# BEP31_RPM_BAR_switchedRES.net
KiCad netlist of a schematic drawn in EAGLE
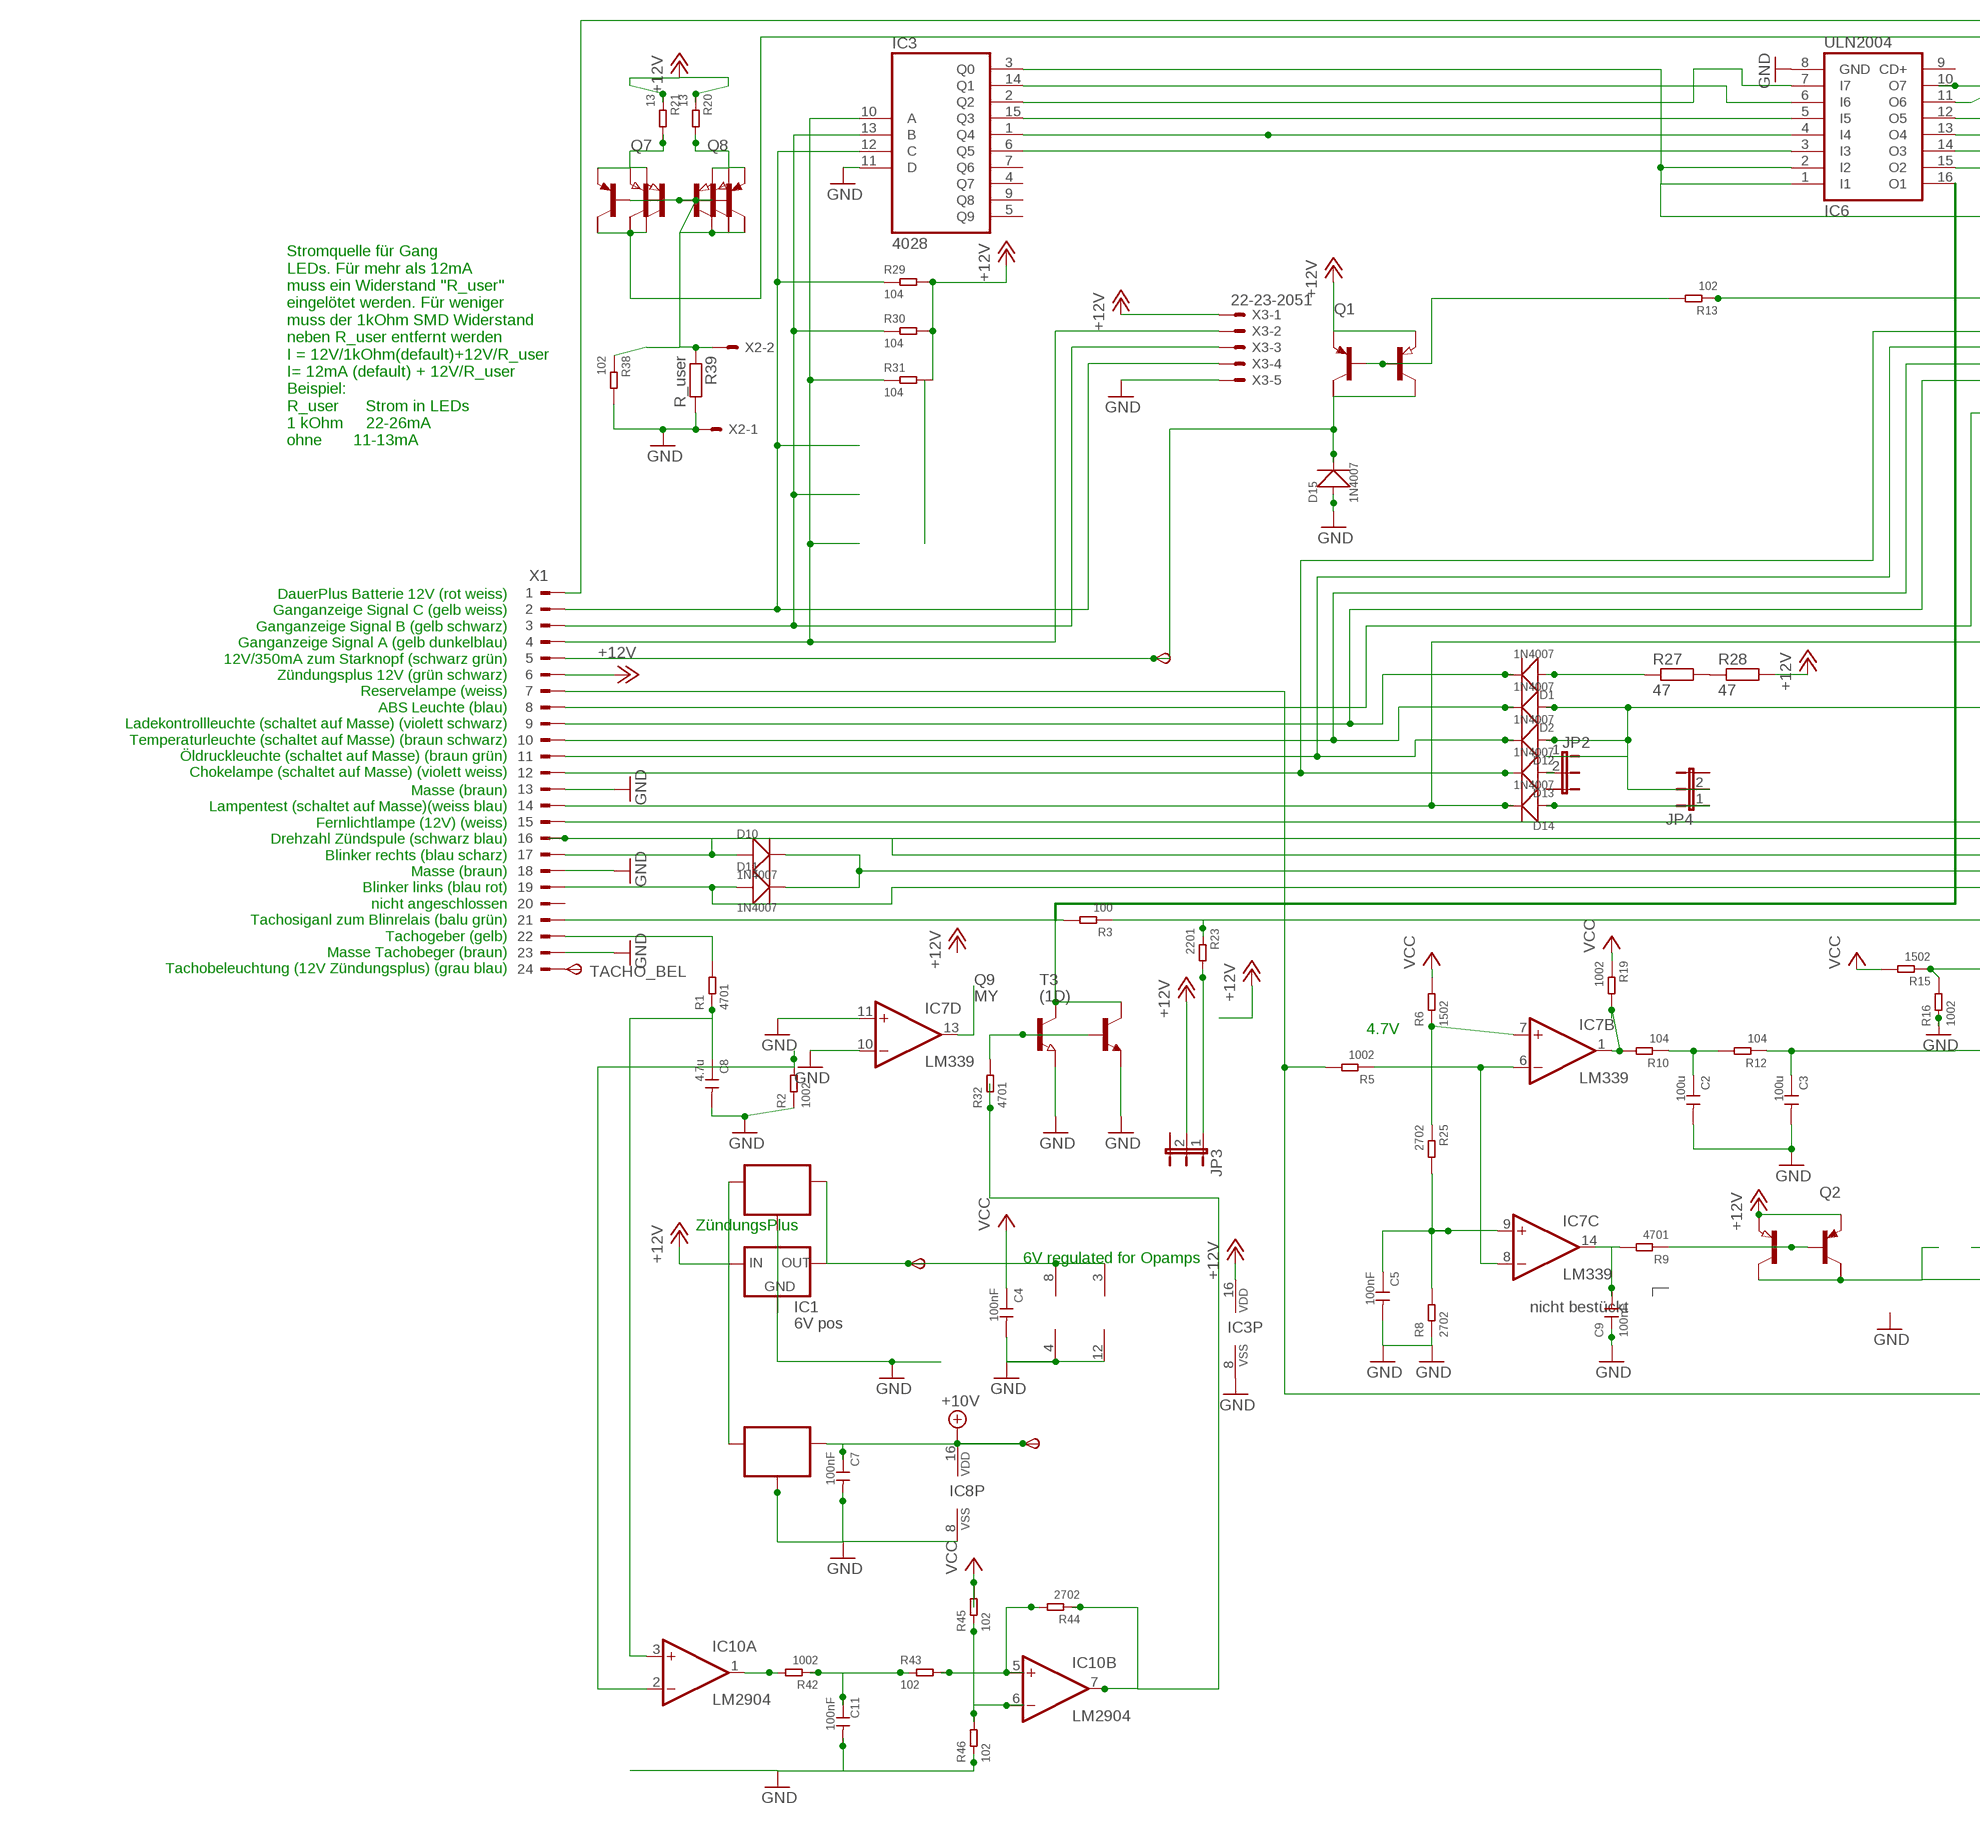
[diagram p0: schematic, sheet 1, part 1 of 2]
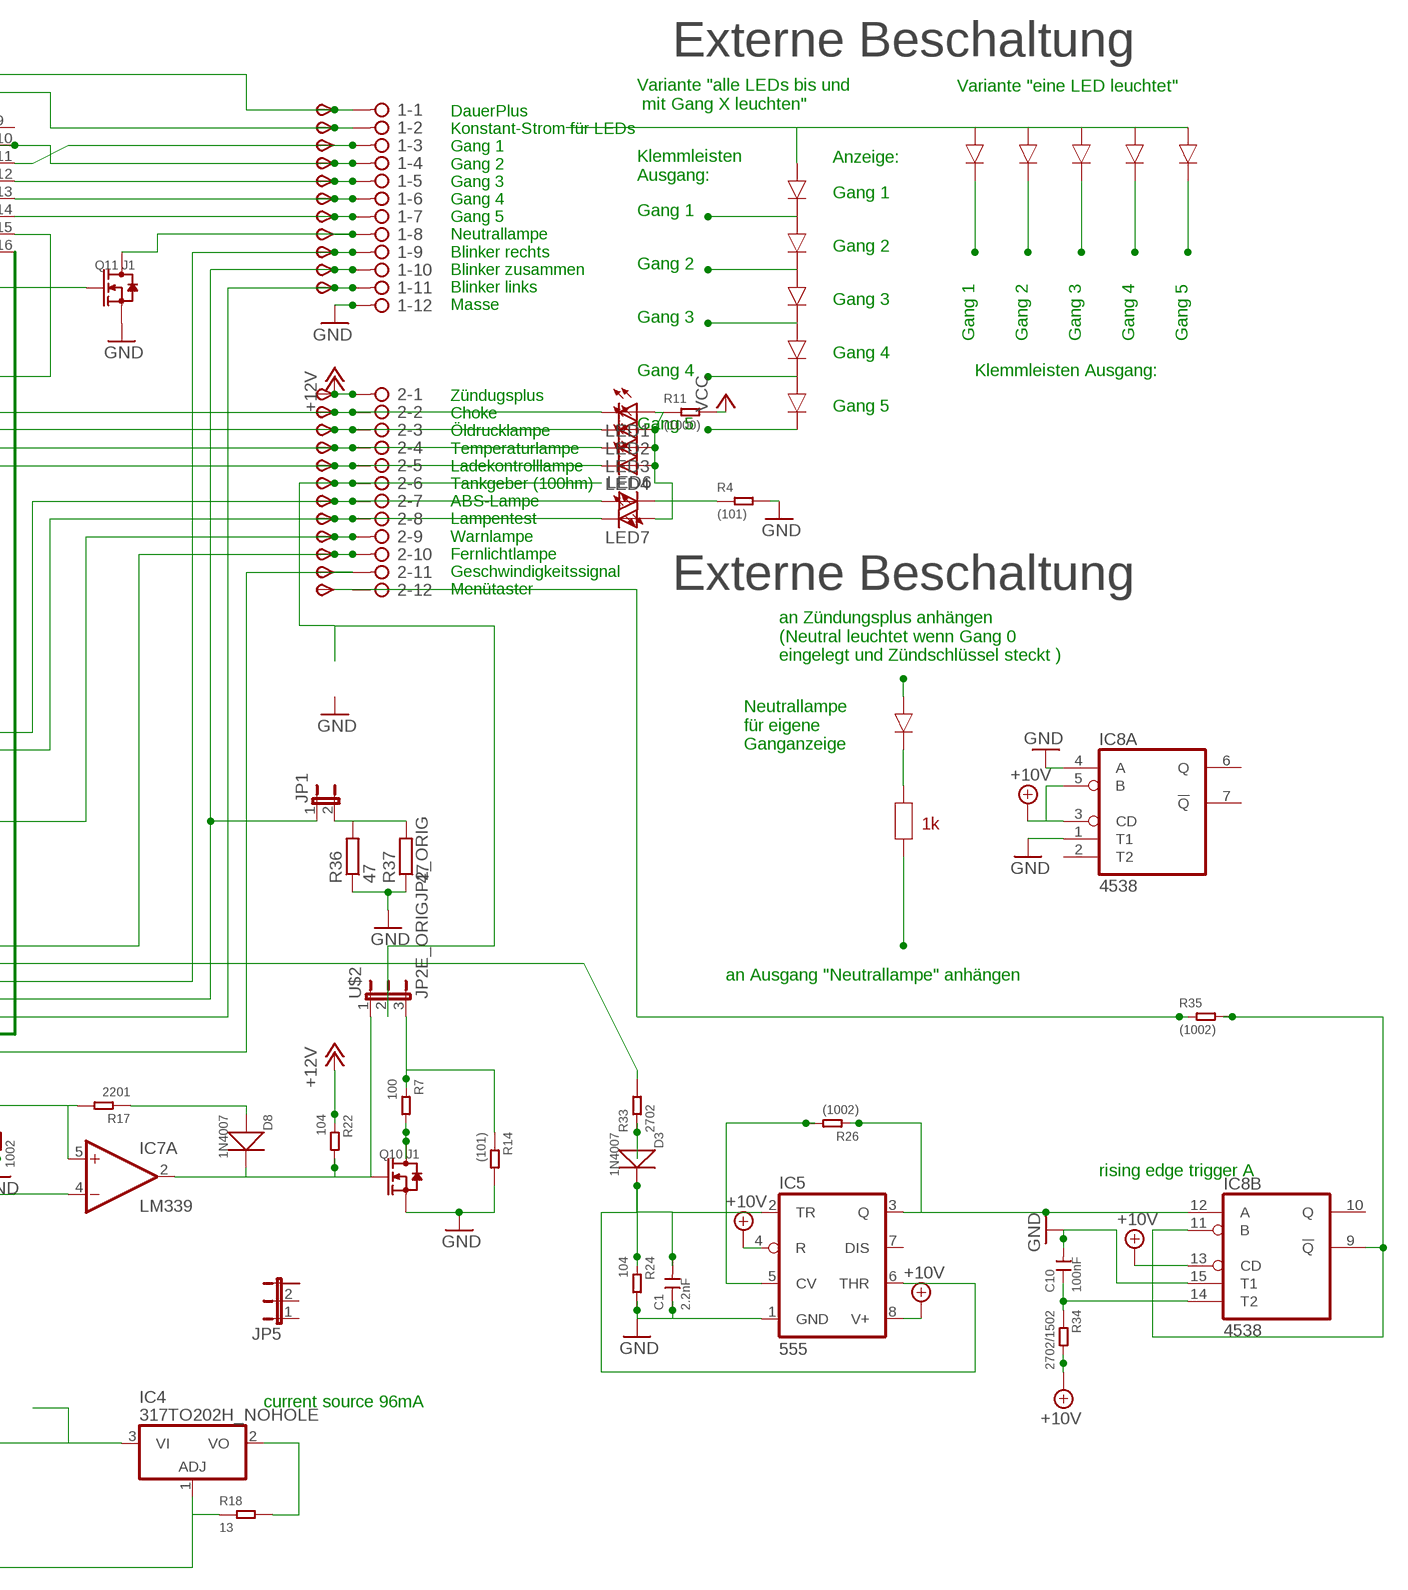
[diagram p1: schematic, sheet 1, part 2 of 2]

(export (version "E")
  (design (tool "Eeschema 10.0.6"))
  (components
    (comp (ref "1")
      (value "2081-1132")
      (footprint "eagle-import:12-PIN")
      (libsource (lib "eagle-import") (part "2081-1132"))
    )
    (comp (ref "2")
      (value "2081-1132")
      (footprint "eagle-import:12-PIN")
      (libsource (lib "eagle-import") (part "2081-1132"))
    )
    (comp (ref "6V")
      (value "TPSB1.8")
      (footprint "eagle-import:B1.8")
      (libsource (lib "eagle-import") (part "TPSB1.8"))
    )
    (comp (ref "10V")
      (value "TPSB1.8")
      (footprint "eagle-import:B1.8")
      (libsource (lib "eagle-import") (part "TPSB1.8"))
    )
    (comp (ref "C1")
      (value "2.2nF")
      (footprint "eagle-import:C0805")
      (fields (field (name "MPN") "CC0805KRX7R9BB104"))
      (libsource (lib "eagle-import") (part "CERAMIC-100NF-50V-10%-X7R(0805)"))
    )
    (comp (ref "C2")
      (value "100u")
      (footprint "eagle-import:C1206")
      (fields (field (name "MPN") "GRM31CR60J107ME39L"))
      (libsource (lib "eagle-import") (part "CERAMIC-100UF-6.3V-20%-X5R(1206)"))
    )
    (comp (ref "C3")
      (value "100u")
      (footprint "eagle-import:C1206")
      (fields (field (name "MPN") "GRM31CR60J107ME39L"))
      (libsource (lib "eagle-import") (part "CERAMIC-100UF-6.3V-20%-X5R(1206)"))
    )
    (comp (ref "C4")
      (value "100nF")
      (footprint "eagle-import:C0805")
      (fields (field (name "MPN") "CC0805KRX7R9BB104"))
      (libsource (lib "eagle-import") (part "CERAMIC-100NF-50V-10%-X7R(0805)"))
    )
    (comp (ref "C5")
      (value "100nF")
      (footprint "eagle-import:C0805")
      (fields (field (name "MPN") "CC0805KRX7R9BB104"))
      (libsource (lib "eagle-import") (part "CERAMIC-100NF-50V-10%-X7R(0805)"))
    )
    (comp (ref "C7")
      (value "100nF")
      (footprint "eagle-import:C0805")
      (fields (field (name "MPN") "CC0805KRX7R9BB104"))
      (libsource (lib "eagle-import") (part "CERAMIC-100NF-50V-10%-X7R(0805)"))
    )
    (comp (ref "C8")
      (value "4.7u")
      (footprint "eagle-import:C0805")
      (fields (field (name "MPN") "CC0805KKX5R8BB475"))
      (libsource (lib "eagle-import") (part "CERAMIC-4.7UF-25V-10%-X5R(0805)"))
    )
    (comp (ref "C9")
      (value "100nF")
      (footprint "eagle-import:C0805")
      (fields (field (name "MPN") "CC0805KRX7R9BB104"))
      (libsource (lib "eagle-import") (part "CERAMIC-100NF-50V-10%-X7R(0805)"))
    )
    (comp (ref "C10")
      (value "100nF")
      (footprint "eagle-import:C0805")
      (fields (field (name "MPN") "CC0805KRX7R9BB104"))
      (libsource (lib "eagle-import") (part "CERAMIC-100NF-50V-10%-X7R(0805)"))
    )
    (comp (ref "C11")
      (value "100nF")
      (footprint "eagle-import:C0805")
      (fields (field (name "MPN") "CC0805KRX7R9BB104"))
      (libsource (lib "eagle-import") (part "CERAMIC-100NF-50V-10%-X7R(0805)"))
    )
    (comp (ref "D1")
      (value "1N4007")
      (footprint "eagle-import:DO-214AC")
      (libsource (lib "eagle-import") (part "DIODE-GEN-PURPOSE-1KV-1A(DO-214AC)"))
    )
    (comp (ref "D2")
      (value "1N4007")
      (footprint "eagle-import:DO-214AC-1206MOUNT")
      (libsource (lib "eagle-import") (part "DIODE-GEN-PURPOSE-1KV-1A(DO-214AC)DO-214AC/1206"))
    )
    (comp (ref "D3")
      (value "1N4007")
      (footprint "eagle-import:DO-214AC")
      (libsource (lib "eagle-import") (part "DIODE-GEN-PURPOSE-1KV-1A(DO-214AC)"))
    )
    (comp (ref "D8")
      (value "1N4007")
      (footprint "eagle-import:DO-214AC")
      (libsource (lib "eagle-import") (part "DIODE-GEN-PURPOSE-1KV-1A(DO-214AC)"))
    )
    (comp (ref "D10")
      (value "1N4007")
      (footprint "eagle-import:DO-214AC")
      (libsource (lib "eagle-import") (part "DIODE-GEN-PURPOSE-1KV-1A(DO-214AC)"))
    )
    (comp (ref "D11")
      (value "1N4007")
      (footprint "eagle-import:DO-214AC")
      (libsource (lib "eagle-import") (part "DIODE-GEN-PURPOSE-1KV-1A(DO-214AC)"))
    )
    (comp (ref "D12")
      (value "1N4007")
      (footprint "eagle-import:DO-214AC-1206MOUNT")
      (libsource (lib "eagle-import") (part "DIODE-GEN-PURPOSE-1KV-1A(DO-214AC)DO-214AC/1206"))
    )
    (comp (ref "D13")
      (value "1N4007")
      (footprint "eagle-import:DO-214AC-1206MOUNT")
      (libsource (lib "eagle-import") (part "DIODE-GEN-PURPOSE-1KV-1A(DO-214AC)DO-214AC/1206"))
    )
    (comp (ref "D14")
      (value "1N4007")
      (footprint "eagle-import:DO-214AC-1206MOUNT")
      (libsource (lib "eagle-import") (part "DIODE-GEN-PURPOSE-1KV-1A(DO-214AC)DO-214AC/1206"))
    )
    (comp (ref "D15")
      (value "1N4007")
      (footprint "eagle-import:DO-214AC")
      (libsource (lib "eagle-import") (part "DIODE-GEN-PURPOSE-1KV-1A(DO-214AC)"))
    )
    (comp (ref "IC1")
      (value "6V pos")
      (footprint "eagle-import:78LXX")
      (libsource (lib "eagle-import") (part "v-reg_78LXX"))
    )
    (comp (ref "IC2")
      (value "78LXXSOT89_ROUND")
      (footprint "eagle-import:SOT89_ROUND")
      (libsource (lib "eagle-import") (part "78LXXSOT89_ROUND"))
    )
    (comp (ref "IC3")
      (value "4028")
      (footprint "eagle-import:SO16")
      (libsource (lib "eagle-import") (part "4028D"))
    )
    (comp (ref "IC4")
      (value "317TO202H_NOHOLE")
      (footprint "eagle-import:TO220H_NOHOLE")
      (libsource (lib "eagle-import") (part "317TO202H_NOHOLE"))
    )
    (comp (ref "IC5")
      (value "555")
      (footprint "eagle-import:SO08")
      (libsource (lib "eagle-import") (part "555DNE"))
    )
    (comp (ref "IC6")
      (value "ULN2004")
      (footprint "eagle-import:SO16")
      (libsource (lib "eagle-import") (part "ULN2004AD"))
    )
    (comp (ref "IC7")
      (value "LM339")
      (footprint "eagle-import:SO14")
      (libsource (lib "eagle-import") (part "LM339D"))
    )
    (comp (ref "IC8")
      (value "4538")
      (footprint "eagle-import:SO16")
      (libsource (lib "eagle-import") (part "4538D"))
    )
    (comp (ref "IC9")
      (value "78LXXSOT89_ROUND")
      (footprint "eagle-import:SOT89_ROUND")
      (libsource (lib "eagle-import") (part "78LXXSOT89_ROUND"))
    )
    (comp (ref "IC10")
      (value "LM2904")
      (footprint "eagle-import:SO08")
      (libsource (lib "eagle-import") (part "LM358D"))
    )
    (comp (ref "JP1")
      (value "JP1E")
      (footprint "eagle-import:JP1")
      (libsource (lib "eagle-import") (part "JP1E"))
    )
    (comp (ref "JP2")
      (value "JP2E")
      (footprint "eagle-import:JP2")
      (libsource (lib "eagle-import") (part "JP2E"))
    )
    (comp (ref "JP3")
      (value "JP2E")
      (footprint "eagle-import:JP2")
      (libsource (lib "eagle-import") (part "JP2E"))
    )
    (comp (ref "JP4")
      (value "JP2E")
      (footprint "eagle-import:JP2")
      (libsource (lib "eagle-import") (part "JP2E"))
    )
    (comp (ref "JP5")
      (value "JP2E")
      (footprint "eagle-import:JP2")
      (libsource (lib "eagle-import") (part "JP2E"))
    )
    (comp (ref "LED1")
      (value "LEDLD260")
      (footprint "eagle-import:LD260")
      (libsource (lib "eagle-import") (part "LEDLD260"))
    )
    (comp (ref "LED2")
      (value "LEDLD260")
      (footprint "eagle-import:LD260")
      (libsource (lib "eagle-import") (part "LEDLD260"))
    )
    (comp (ref "LED3")
      (value "LEDLD260")
      (footprint "eagle-import:LD260")
      (libsource (lib "eagle-import") (part "LEDLD260"))
    )
    (comp (ref "LED4")
      (value "LEDLD260")
      (footprint "eagle-import:LD260")
      (libsource (lib "eagle-import") (part "LEDLD260"))
    )
    (comp (ref "LED6")
      (value "LEDLD260")
      (footprint "eagle-import:LD260")
      (libsource (lib "eagle-import") (part "LEDLD260"))
    )
    (comp (ref "LED7")
      (value "LEDLD260")
      (footprint "eagle-import:LD260")
      (libsource (lib "eagle-import") (part "LEDLD260"))
    )
    (comp (ref "Q1")
      (value "PNP-TRANSISTOR_SOT89")
      (footprint "eagle-import:SOT89")
      (libsource (lib "eagle-import") (part "PNP-TRANSISTOR_SOT89"))
    )
    (comp (ref "Q2")
      (value "PNP-TRANSISTOR_SOT89")
      (footprint "eagle-import:SOT89")
      (libsource (lib "eagle-import") (part "PNP-TRANSISTOR_SOT89"))
    )
    (comp (ref "Q3")
      (value "AH-16")
      (footprint "eagle-import:SOT223")
      (libsource (lib "eagle-import") (part "BCP53T1"))
    )
    (comp (ref "Q4")
      (value "(AH-16)")
      (footprint "eagle-import:SOT223")
      (libsource (lib "eagle-import") (part "BCP53T1"))
    )
    (comp (ref "Q5")
      (value "(AH-16)")
      (footprint "eagle-import:SOT223")
      (libsource (lib "eagle-import") (part "BCP53T1"))
    )
    (comp (ref "Q6")
      (value "(AH-16)")
      (footprint "eagle-import:SOT223")
      (libsource (lib "eagle-import") (part "BCP53T1"))
    )
    (comp (ref "Q7")
      (value "PNP-TRANSISTOR_SOT89")
      (footprint "eagle-import:SOT89")
      (libsource (lib "eagle-import") (part "PNP-TRANSISTOR_SOT89"))
    )
    (comp (ref "Q8")
      (value "PNP-TRANSISTOR_SOT89")
      (footprint "eagle-import:SOT89")
      (libsource (lib "eagle-import") (part "PNP-TRANSISTOR_SOT89"))
    )
    (comp (ref "Q9")
      (value "MY")
      (footprint "eagle-import:SOT89")
      (libsource (lib "eagle-import") (part "NPN-TRANSISTOR_SOT89"))
    )
    (comp (ref "Q10")
      (value "J1")
      (footprint "eagle-import:SOT-23")
      (fields (field (name "MPN") "BSS138W-7-F"))
      (libsource (lib "eagle-import") (part "SMD-MOSFET-N-CH-50V-200MA-BSS138W-7-F(SOT-23)"))
    )
    (comp (ref "Q11")
      (value "J1")
      (footprint "eagle-import:SOT-23")
      (fields (field (name "MPN") "BSS138W-7-F"))
      (libsource (lib "eagle-import") (part "SMD-MOSFET-N-CH-50V-200MA-BSS138W-7-F(SOT-23)"))
    )
    (comp (ref "R1")
      (value "4701")
      (footprint "eagle-import:R0805")
      (fields (field (name "MPN") "RC0805JR-074K7L"))
      (libsource (lib "eagle-import") (part "SMD-RES-4.7K-5%-1/8W(0805)"))
    )
    (comp (ref "R2")
      (value "1002")
      (footprint "eagle-import:R0805")
      (fields (field (name "MPN") "RC0805FR-0710KL"))
      (libsource (lib "eagle-import") (part "SMD-RES-10K-1%-1/8W(0805)"))
    )
    (comp (ref "R3")
      (value "100")
      (footprint "eagle-import:R0805")
      (fields (field (name "MPN") "RC0805JR-07220RL"))
      (libsource (lib "eagle-import") (part "SMD-RES-220R-5%-1/8W(0805)"))
    )
    (comp (ref "R4")
      (value "(101)")
      (footprint "eagle-import:R0805")
      (fields (field (name "MPN") "RC0805JR-07100RL"))
      (libsource (lib "eagle-import") (part "SMD-RES-100R-5%-1/8W(0805)"))
    )
    (comp (ref "R5")
      (value "1002")
      (footprint "eagle-import:R0805")
      (fields (field (name "MPN") "RC0805FR-0710KL"))
      (libsource (lib "eagle-import") (part "SMD-RES-10K-1%-1/8W(0805)"))
    )
    (comp (ref "R6")
      (value "1502")
      (footprint "eagle-import:R0805")
      (fields (field (name "MPN") "RC0805FR-0710KL"))
      (libsource (lib "eagle-import") (part "SMD-RES-10K-1%-1/8W(0805)"))
    )
    (comp (ref "R7")
      (value "100")
      (footprint "eagle-import:R0805")
      (fields (field (name "MPN") "RC0805JR-072K2L"))
      (libsource (lib "eagle-import") (part "SMD-RES-2.2K-5%-1/8W(0805)"))
    )
    (comp (ref "R8")
      (value "2702")
      (footprint "eagle-import:R0805")
      (fields (field (name "MPN") "RC0805JR-074K7L"))
      (libsource (lib "eagle-import") (part "SMD-RES-4.7K-5%-1/8W(0805)"))
    )
    (comp (ref "R9")
      (value "4701")
      (footprint "eagle-import:R0805")
      (fields (field (name "MPN") "RC0805JR-074K7L"))
      (libsource (lib "eagle-import") (part "SMD-RES-4.7K-5%-1/8W(0805)"))
    )
    (comp (ref "R10")
      (value "104")
      (footprint "eagle-import:R0805")
      (fields (field (name "MPN") "RC0805FR-0710KL"))
      (libsource (lib "eagle-import") (part "SMD-RES-10K-1%-1/8W(0805)"))
    )
    (comp (ref "R11")
      (value "(1000)")
      (footprint "eagle-import:R0805")
      (fields (field (name "MPN") "RC0805JR-07100RL"))
      (libsource (lib "eagle-import") (part "SMD-RES-100R-5%-1/8W(0805)"))
    )
    (comp (ref "R12")
      (value "104")
      (footprint "eagle-import:R0805")
      (fields (field (name "MPN") "RC0805FR-0710KL"))
      (libsource (lib "eagle-import") (part "SMD-RES-10K-1%-1/8W(0805)"))
    )
    (comp (ref "R13")
      (value "102")
      (footprint "eagle-import:R0805")
      (fields (field (name "MPN") "RC0805JR-071KL"))
      (libsource (lib "eagle-import") (part "SMD-RES-1K-5%-1/8W(0805)"))
    )
    (comp (ref "R14")
      (value "(101)")
      (footprint "eagle-import:R0805")
      (fields (field (name "MPN") "RC0805JR-072K2L"))
      (libsource (lib "eagle-import") (part "SMD-RES-2.2K-5%-1/8W(0805)"))
    )
    (comp (ref "R15")
      (value "1502")
      (footprint "eagle-import:R0805")
      (fields (field (name "MPN") "RC0805FR-0710KL"))
      (libsource (lib "eagle-import") (part "SMD-RES-10K-1%-1/8W(0805)"))
    )
    (comp (ref "R16")
      (value "1002")
      (footprint "eagle-import:R0805")
      (fields (field (name "MPN") "RC0805FR-0710KL"))
      (libsource (lib "eagle-import") (part "SMD-RES-10K-1%-1/8W(0805)"))
    )
    (comp (ref "R17")
      (value "2201")
      (footprint "eagle-import:R0805")
      (fields (field (name "MPN") "RC0805JR-072K2L"))
      (libsource (lib "eagle-import") (part "SMD-RES-2.2K-5%-1/8W(0805)"))
    )
    (comp (ref "R18")
      (value "13")
      (footprint "eagle-import:R1206")
      (fields (field (name "MPN") "RC1206JR-0713RL"))
      (libsource (lib "eagle-import") (part "SMD-RES-13R-5%-1/4W(1206)"))
    )
    (comp (ref "R19")
      (value "1002")
      (footprint "eagle-import:R0805")
      (fields (field (name "MPN") "RC0805FR-0710KL"))
      (libsource (lib "eagle-import") (part "SMD-RES-10K-1%-1/8W(0805)"))
    )
    (comp (ref "R20")
      (value "13")
      (footprint "eagle-import:R1206")
      (fields (field (name "MPN") "RC1206JR-0713RL"))
      (libsource (lib "eagle-import") (part "SMD-RES-13R-5%-1/4W(1206)"))
    )
    (comp (ref "R21")
      (value "13")
      (footprint "eagle-import:R1206")
      (fields (field (name "MPN") "RC1206JR-0713RL"))
      (libsource (lib "eagle-import") (part "SMD-RES-13R-5%-1/4W(1206)"))
    )
    (comp (ref "R22")
      (value "104")
      (footprint "eagle-import:R0805")
      (fields (field (name "MPN") "RC0805FR-0710KL"))
      (libsource (lib "eagle-import") (part "SMD-RES-10K-1%-1/8W(0805)"))
    )
    (comp (ref "R23")
      (value "2201")
      (footprint "eagle-import:R0805")
      (fields (field (name "MPN") "RC0805JR-072K2L"))
      (libsource (lib "eagle-import") (part "SMD-RES-2.2K-5%-1/8W(0805)"))
    )
    (comp (ref "R24")
      (value "104")
      (footprint "eagle-import:R0805")
      (fields (field (name "MPN") "RC0805FR-0710KL"))
      (libsource (lib "eagle-import") (part "SMD-RES-10K-1%-1/8W(0805)"))
    )
    (comp (ref "R25")
      (value "2702")
      (footprint "eagle-import:R0805")
      (fields (field (name "MPN") "RC0805JR-074K7L"))
      (libsource (lib "eagle-import") (part "SMD-RES-4.7K-5%-1/8W(0805)"))
    )
    (comp (ref "R26")
      (value "(1002)")
      (footprint "eagle-import:R0805")
      (fields (field (name "MPN") "RC0805FR-0710KL"))
      (libsource (lib "eagle-import") (part "SMD-RES-10K-1%-1/8W(0805)"))
    )
    (comp (ref "R27")
      (value "47")
      (footprint "eagle-import:V235_17_1MM")
      (libsource (lib "eagle-import") (part "R-EU_V235/17_1MM"))
    )
    (comp (ref "R28")
      (value "47")
      (footprint "eagle-import:V235_17_1MM")
      (libsource (lib "eagle-import") (part "R-EU_V235/17_1MM"))
    )
    (comp (ref "R29")
      (value "104")
      (footprint "eagle-import:R0805")
      (fields (field (name "MPN") "RC0805FR-0710KL"))
      (libsource (lib "eagle-import") (part "SMD-RES-10K-1%-1/8W(0805)"))
    )
    (comp (ref "R30")
      (value "104")
      (footprint "eagle-import:R0805")
      (fields (field (name "MPN") "RC0805FR-0710KL"))
      (libsource (lib "eagle-import") (part "SMD-RES-10K-1%-1/8W(0805)"))
    )
    (comp (ref "R31")
      (value "104")
      (footprint "eagle-import:R0805")
      (fields (field (name "MPN") "RC0805FR-0710KL"))
      (libsource (lib "eagle-import") (part "SMD-RES-10K-1%-1/8W(0805)"))
    )
    (comp (ref "R32")
      (value "4701")
      (footprint "eagle-import:R0805")
      (fields (field (name "MPN") "RC0805JR-074K7L"))
      (libsource (lib "eagle-import") (part "SMD-RES-4.7K-5%-1/8W(0805)"))
    )
    (comp (ref "R33")
      (value "2702")
      (footprint "eagle-import:R0805")
      (fields (field (name "MPN") "RC0805FR-0710KL"))
      (libsource (lib "eagle-import") (part "SMD-RES-10K-1%-1/8W(0805)"))
    )
    (comp (ref "R34")
      (value "2702/1502")
      (footprint "eagle-import:R0805")
      (fields (field (name "MPN") "RC0805JR-074K7L"))
      (libsource (lib "eagle-import") (part "SMD-RES-4.7K-5%-1/8W(0805)"))
    )
    (comp (ref "R35")
      (value "(1002)")
      (footprint "eagle-import:R0805")
      (fields (field (name "MPN") "RC0805JR-074K7L"))
      (libsource (lib "eagle-import") (part "SMD-RES-4.7K-5%-1/8W(0805)"))
    )
    (comp (ref "R36")
      (value "47")
      (footprint "eagle-import:V235_17_1MM")
      (libsource (lib "eagle-import") (part "R-EU_V235/17_1MM"))
    )
    (comp (ref "R37")
      (value "47")
      (footprint "eagle-import:V235_17_1MM")
      (libsource (lib "eagle-import") (part "R-EU_V235/17_1MM"))
    )
    (comp (ref "R38")
      (value "102")
      (footprint "eagle-import:R0805")
      (fields (field (name "MPN") "RC0805JR-071KL"))
      (libsource (lib "eagle-import") (part "SMD-RES-1K-5%-1/8W(0805)"))
    )
    (comp (ref "R39")
      (value "R_user")
      (footprint "eagle-import:R0805")
      (libsource (lib "eagle-import") (part "R-EU_R0805"))
    )
    (comp (ref "R42")
      (value "1002")
      (footprint "eagle-import:R0805")
      (fields (field (name "MPN") "RC0805FR-0710KL"))
      (libsource (lib "eagle-import") (part "SMD-RES-10K-1%-1/8W(0805)"))
    )
    (comp (ref "R43")
      (value "102")
      (footprint "eagle-import:R0805")
      (fields (field (name "MPN") "RC0805JR-071KL"))
      (libsource (lib "eagle-import") (part "SMD-RES-1K-5%-1/8W(0805)"))
    )
    (comp (ref "R44")
      (value "2702")
      (footprint "eagle-import:R0805")
      (fields (field (name "MPN") "RC0805JR-074K7L"))
      (libsource (lib "eagle-import") (part "SMD-RES-4.7K-5%-1/8W(0805)"))
    )
    (comp (ref "R45")
      (value "102")
      (footprint "eagle-import:R0805")
      (fields (field (name "MPN") "RC0805JR-071KL"))
      (libsource (lib "eagle-import") (part "SMD-RES-1K-5%-1/8W(0805)"))
    )
    (comp (ref "R46")
      (value "102")
      (footprint "eagle-import:R0805")
      (fields (field (name "MPN") "RC0805JR-071KL"))
      (libsource (lib "eagle-import") (part "SMD-RES-1K-5%-1/8W(0805)"))
    )
    (comp (ref "START")
      (value "TPSB1.8")
      (footprint "eagle-import:B1.8")
      (libsource (lib "eagle-import") (part "TPSB1.8"))
    )
    (comp (ref "T1")
      (value "PNP2SM8")
      (footprint "eagle-import:SM8")
      (libsource (lib "eagle-import") (part "PNP2SM8"))
    )
    (comp (ref "T3")
      (value "(1D)")
      (footprint "eagle-import:SOT23-BEC")
      (libsource (lib "eagle-import") (part "-NPN-SOT23-BECMMBTA42LT1"))
    )
    (comp (ref "TACHO_BEL")
      (value "TPSP1_1MM")
      (footprint "eagle-import:P1_1.0MM")
      (libsource (lib "eagle-import") (part "TPSP1_1MM"))
    )
    (comp (ref "TP1")
      (value "TPSB1.8")
      (footprint "eagle-import:B1.8")
      (libsource (lib "eagle-import") (part "TPSB1.8"))
    )
    (comp (ref "TP2")
      (value "TPSB1.8")
      (footprint "eagle-import:B1.8")
      (libsource (lib "eagle-import") (part "TPSB1.8"))
    )
    (comp (ref "TP3")
      (value "TPSB1.8")
      (footprint "eagle-import:B1.8")
      (libsource (lib "eagle-import") (part "TPSB1.8"))
    )
    (comp (ref "TP4")
      (value "TPSB1.8")
      (footprint "eagle-import:B1.8")
      (libsource (lib "eagle-import") (part "TPSB1.8"))
    )
    (comp (ref "TP5")
      (value "TPSB1.8")
      (footprint "eagle-import:B1.8")
      (libsource (lib "eagle-import") (part "TPSB1.8"))
    )
    (comp (ref "TP6")
      (value "TPSB1.8")
      (footprint "eagle-import:B1.8")
      (libsource (lib "eagle-import") (part "TPSB1.8"))
    )
    (comp (ref "TP7")
      (value "TPSB1.8")
      (footprint "eagle-import:B1.8")
      (libsource (lib "eagle-import") (part "TPSB1.8"))
    )
    (comp (ref "TP8")
      (value "TPSB1.8")
      (footprint "eagle-import:B1.8")
      (libsource (lib "eagle-import") (part "TPSB1.8"))
    )
    (comp (ref "TP9")
      (value "TPSB1.8")
      (footprint "eagle-import:B1.8")
      (libsource (lib "eagle-import") (part "TPSB1.8"))
    )
    (comp (ref "TP10")
      (value "TPSB1.8")
      (footprint "eagle-import:B1.8")
      (libsource (lib "eagle-import") (part "TPSB1.8"))
    )
    (comp (ref "TP11")
      (value "TPSB1.8")
      (footprint "eagle-import:B1.8")
      (libsource (lib "eagle-import") (part "TPSB1.8"))
    )
    (comp (ref "TP12")
      (value "TPSB1.8")
      (footprint "eagle-import:B1.8")
      (libsource (lib "eagle-import") (part "TPSB1.8"))
    )
    (comp (ref "TP13")
      (value "TPSB1,27")
      (footprint "eagle-import:B1,27")
      (libsource (lib "eagle-import") (part "TPSB1,27"))
    )
    (comp (ref "TP16")
      (value "TPSB1.8")
      (footprint "eagle-import:B1.8")
      (libsource (lib "eagle-import") (part "TPSB1.8"))
    )
    (comp (ref "TP17")
      (value "TPSB1.8")
      (footprint "eagle-import:B1.8")
      (libsource (lib "eagle-import") (part "TPSB1.8"))
    )
    (comp (ref "TP18")
      (value "TPSB1.8")
      (footprint "eagle-import:B1.8")
      (libsource (lib "eagle-import") (part "TPSB1.8"))
    )
    (comp (ref "TP19")
      (value "TPSB1.8")
      (footprint "eagle-import:B1.8")
      (libsource (lib "eagle-import") (part "TPSB1.8"))
    )
    (comp (ref "TP21")
      (value "TPSB1.8")
      (footprint "eagle-import:B1.8")
      (libsource (lib "eagle-import") (part "TPSB1.8"))
    )
    (comp (ref "TP22")
      (value "TPSB1.8")
      (footprint "eagle-import:B1.8")
      (libsource (lib "eagle-import") (part "TPSB1.8"))
    )
    (comp (ref "TP23")
      (value "TPSB1.8")
      (footprint "eagle-import:B1.8")
      (libsource (lib "eagle-import") (part "TPSB1.8"))
    )
    (comp (ref "TP24")
      (value "TPSB1,27")
      (footprint "eagle-import:B1,27")
      (libsource (lib "eagle-import") (part "TPSB1,27"))
    )
    (comp (ref "TP25")
      (value "TPSB1.8")
      (footprint "eagle-import:B1.8")
      (libsource (lib "eagle-import") (part "TPSB1.8"))
    )
    (comp (ref "TP26")
      (value "TPSB1.8")
      (footprint "eagle-import:B1.8")
      (libsource (lib "eagle-import") (part "TPSB1.8"))
    )
    (comp (ref "U$2")
      (value "JP2E_ORIGJP2_ORIG")
      (footprint "eagle-import:JP2_ORIG")
      (libsource (lib "eagle-import") (part "JP2E_ORIGJP2_ORIG"))
    )
    (comp (ref "X1")
      (value "CON_BMWV2")
      (footprint "eagle-import:24-PIN_V2")
      (libsource (lib "eagle-import") (part "CON_BMWV2"))
    )
    (comp (ref "X2")
      (value "22-23-2021")
      (footprint "eagle-import:22-23-2021")
      (fields (field (name "MF") "MOLEX"))
      (libsource (lib "eagle-import") (part "22-23-2021"))
    )
    (comp (ref "X3")
      (value "22-23-2051")
      (footprint "eagle-import:22-23-2051")
      (fields (field (name "MF") "MOLEX"))
      (libsource (lib "eagle-import") (part "22-23-2051"))
    )
  )
  (nets
    (net (code "1") (name "+10V") (class "Default")
      (node (ref "10V") (pin "TP") (pinfunction "PP_TP") (pintype "input"))
      (node (ref "C7") (pin "1") (pinfunction "1_1") (pintype "passive"))
      (node (ref "IC5") (pin "4") (pinfunction "R_4") (pintype "input"))
      (node (ref "IC5") (pin "8") (pinfunction "V+_8") (pintype "power_in"))
      (node (ref "IC8") (pin "13") (pinfunction "CD_13") (pintype "input"))
      (node (ref "IC8") (pin "16") (pinfunction "VDD_16") (pintype "power_in"))
      (node (ref "IC8") (pin "3") (pinfunction "CD_3") (pintype "input"))
      (node (ref "IC8") (pin "5") (pinfunction "B_5") (pintype "input"))
      (node (ref "IC9") (pin "1") (pinfunction "OUT_1") (pintype "passive"))
      (node (ref "R34") (pin "2") (pinfunction "2_2") (pintype "passive"))
    )
    (net (code "2") (name "+12V") (class "Default")
      (node (ref "2") (pin "1") (pinfunction "KL_1") (pintype "passive"))
      (node (ref "IC1") (pin "IN") (pinfunction "IN_IN") (pintype "input"))
      (node (ref "IC2") (pin "3") (pinfunction "IN_3") (pintype "input"))
      (node (ref "IC3") (pin "16") (pinfunction "VDD_16") (pintype "power_in"))
      (node (ref "IC9") (pin "3") (pinfunction "IN_3") (pintype "input"))
      (node (ref "JP3") (pin "2") (pinfunction "2_2") (pintype "passive"))
      (node (ref "Q1") (pin "3") (pinfunction "E_3") (pintype "passive"))
      (node (ref "Q2") (pin "3") (pinfunction "E_3") (pintype "passive"))
      (node (ref "Q3") (pin "3") (pinfunction "E_3") (pintype "passive"))
      (node (ref "Q4") (pin "3") (pinfunction "E_3") (pintype "passive"))
      (node (ref "R20") (pin "1") (pinfunction "1_1") (pintype "passive"))
      (node (ref "R21") (pin "1") (pinfunction "1_1") (pintype "passive"))
      (node (ref "R22") (pin "1") (pinfunction "1_1") (pintype "passive"))
      (node (ref "R28") (pin "2") (pinfunction "2_2") (pintype "passive"))
      (node (ref "R29") (pin "2") (pinfunction "2_2") (pintype "passive"))
      (node (ref "R30") (pin "2") (pinfunction "2_2") (pintype "passive"))
      (node (ref "R31") (pin "2") (pinfunction "2_2") (pintype "passive"))
      (node (ref "TP12") (pin "TP") (pinfunction "PP_TP") (pintype "input"))
      (node (ref "X1") (pin "6") (pinfunction "6_6") (pintype "passive"))
      (node (ref "X3") (pin "1") (pinfunction "S_1") (pintype "passive"))
    )
    (net (code "3") (name "GND") (class "Default")
      (node (ref "1") (pin "12") (pinfunction "KL_12") (pintype "passive"))
      (node (ref "C1") (pin "1") (pinfunction "1_1") (pintype "passive"))
      (node (ref "C10") (pin "2") (pinfunction "2_2") (pintype "passive"))
      (node (ref "C11") (pin "2") (pinfunction "2_2") (pintype "passive"))
      (node (ref "C2") (pin "2") (pinfunction "2_2") (pintype "passive"))
      (node (ref "C3") (pin "2") (pinfunction "2_2") (pintype "passive"))
      (node (ref "C4") (pin "2") (pinfunction "2_2") (pintype "passive"))
      (node (ref "C5") (pin "2") (pinfunction "2_2") (pintype "passive"))
      (node (ref "C7") (pin "2") (pinfunction "2_2") (pintype "passive"))
      (node (ref "C8") (pin "2") (pinfunction "2_2") (pintype "passive"))
      (node (ref "C9") (pin "1") (pinfunction "1_1") (pintype "passive"))
      (node (ref "D15") (pin "1") (pinfunction "+_1") (pintype "passive"))
      (node (ref "IC1") (pin "GND") (pinfunction "GND_GND") (pintype "input"))
      (node (ref "IC10") (pin "4") (pinfunction "V-_4") (pintype "power_in"))
      (node (ref "IC2") (pin "2") (pinfunction "GND_2") (pintype "input"))
      (node (ref "IC2") (pin "2@1") (pinfunction "GND_2@1") (pintype "input"))
      (node (ref "IC3") (pin "11") (pinfunction "D_11") (pintype "input"))
      (node (ref "IC3") (pin "8") (pinfunction "VSS_8") (pintype "power_in"))
      (node (ref "IC5") (pin "1") (pinfunction "GND_1") (pintype "power_in"))
      (node (ref "IC6") (pin "8") (pinfunction "GND_8") (pintype "power_in"))
      (node (ref "IC7") (pin "10") (pinfunction "-IN_10") (pintype "input"))
      (node (ref "IC7") (pin "11") (pinfunction "+IN_11") (pintype "input"))
      (node (ref "IC7") (pin "12") (pinfunction "GND_12") (pintype "power_in"))
      (node (ref "IC8") (pin "1") (pinfunction "T1_1") (pintype "input"))
      (node (ref "IC8") (pin "15") (pinfunction "T1_15") (pintype "input"))
      (node (ref "IC8") (pin "4") (pinfunction "A_4") (pintype "input"))
      (node (ref "IC8") (pin "8") (pinfunction "VSS_8") (pintype "power_in"))
      (node (ref "IC9") (pin "2") (pinfunction "GND_2") (pintype "input"))
      (node (ref "IC9") (pin "2@1") (pinfunction "GND_2@1") (pintype "input"))
      (node (ref "Q10") (pin "2") (pinfunction "S_2") (pintype "passive"))
      (node (ref "Q11") (pin "2") (pinfunction "S_2") (pintype "passive"))
      (node (ref "Q9") (pin "3") (pinfunction "E_3") (pintype "passive"))
      (node (ref "R14") (pin "2") (pinfunction "2_2") (pintype "passive"))
      (node (ref "R16") (pin "1") (pinfunction "1_1") (pintype "passive"))
      (node (ref "R2") (pin "1") (pinfunction "1_1") (pintype "passive"))
      (node (ref "R24") (pin "2") (pinfunction "2_2") (pintype "passive"))
      (node (ref "R36") (pin "1") (pinfunction "1_1") (pintype "passive"))
      (node (ref "R37") (pin "1") (pinfunction "1_1") (pintype "passive"))
      (node (ref "R38") (pin "2") (pinfunction "2_2") (pintype "passive"))
      (node (ref "R39") (pin "2") (pinfunction "2_2") (pintype "passive"))
      (node (ref "R4") (pin "2") (pinfunction "2_2") (pintype "passive"))
      (node (ref "R46") (pin "1") (pinfunction "1_1") (pintype "passive"))
      (node (ref "R8") (pin "1") (pinfunction "1_1") (pintype "passive"))
      (node (ref "T3") (pin "E") (pinfunction "E_E") (pintype "passive"))
      (node (ref "X1") (pin "13") (pinfunction "13_13") (pintype "passive"))
      (node (ref "X1") (pin "18") (pinfunction "18_18") (pintype "passive"))
      (node (ref "X1") (pin "23") (pinfunction "23_23") (pintype "passive"))
      (node (ref "X2") (pin "1") (pinfunction "S_1") (pintype "passive"))
      (node (ref "X3") (pin "5") (pinfunction "S_5") (pintype "passive"))
    )
    (net (code "4") (name "Net-(1A-KL)") (class "Default")
      (node (ref "1") (pin "1") (pinfunction "KL_1") (pintype "passive"))
      (node (ref "TP1") (pin "TP") (pinfunction "PP_TP") (pintype "input"))
      (node (ref "X1") (pin "1") (pinfunction "1_1") (pintype "passive"))
    )
    (net (code "5") (name "Net-(1B-KL)") (class "Default")
      (node (ref "1") (pin "10") (pinfunction "KL_10") (pintype "passive"))
      (node (ref "D10") (pin "2") (pinfunction "-_2") (pintype "passive"))
      (node (ref "D11") (pin "2") (pinfunction "-_2") (pintype "passive"))
      (node (ref "JP1") (pin "1") (pinfunction "1_1") (pintype "passive"))
      (node (ref "TP10") (pin "TP") (pinfunction "PP_TP") (pintype "input"))
    )
    (net (code "6") (name "Net-(1C-KL)") (class "Default")
      (node (ref "1") (pin "11") (pinfunction "KL_11") (pintype "passive"))
      (node (ref "D11") (pin "1") (pinfunction "+_1") (pintype "passive"))
      (node (ref "TP11") (pin "TP") (pinfunction "PP_TP") (pintype "input"))
      (node (ref "X1") (pin "19") (pinfunction "19_19") (pintype "passive"))
    )
    (net (code "7") (name "Net-(1E-KL)") (class "Default")
      (node (ref "1") (pin "2") (pinfunction "KL_2") (pintype "passive"))
      (node (ref "Q5") (pin "2") (pinfunction "C_2") (pintype "passive"))
      (node (ref "Q8") (pin "2") (pinfunction "C_2") (pintype "passive"))
      (node (ref "T1") (pin "8") (pinfunction "C1_8") (pintype "passive"))
      (node (ref "TP2") (pin "TP") (pinfunction "PP_TP") (pintype "input"))
    )
    (net (code "8") (name "Net-(1F-KL)") (class "Default")
      (node (ref "1") (pin "3") (pinfunction "KL_3") (pintype "passive"))
      (node (ref "IC6") (pin "11") (pinfunction "O6_11") (pintype "open_collector"))
      (node (ref "TP3") (pin "TP") (pinfunction "PP_TP") (pintype "input"))
    )
    (net (code "9") (name "Net-(1G-KL)") (class "Default")
      (node (ref "1") (pin "4") (pinfunction "KL_4") (pintype "passive"))
      (node (ref "IC6") (pin "10") (pinfunction "O7_10") (pintype "open_collector"))
      (node (ref "TP4") (pin "TP") (pinfunction "PP_TP") (pintype "input"))
    )
    (net (code "10") (name "Net-(1H-KL)") (class "Default")
      (node (ref "1") (pin "5") (pinfunction "KL_5") (pintype "passive"))
      (node (ref "IC6") (pin "12") (pinfunction "O5_12") (pintype "open_collector"))
      (node (ref "TP5") (pin "TP") (pinfunction "PP_TP") (pintype "input"))
    )
    (net (code "11") (name "Net-(1I-KL)") (class "Default")
      (node (ref "1") (pin "6") (pinfunction "KL_6") (pintype "passive"))
      (node (ref "IC6") (pin "13") (pinfunction "O4_13") (pintype "open_collector"))
      (node (ref "TP6") (pin "TP") (pinfunction "PP_TP") (pintype "input"))
    )
    (net (code "12") (name "Net-(1J-KL)") (class "Default")
      (node (ref "1") (pin "7") (pinfunction "KL_7") (pintype "passive"))
      (node (ref "IC6") (pin "14") (pinfunction "O3_14") (pintype "open_collector"))
      (node (ref "TP7") (pin "TP") (pinfunction "PP_TP") (pintype "input"))
    )
    (net (code "13") (name "Net-(1K-KL)") (class "Default")
      (node (ref "1") (pin "8") (pinfunction "KL_8") (pintype "passive"))
      (node (ref "Q11") (pin "3") (pinfunction "D_3") (pintype "passive"))
      (node (ref "TP8") (pin "TP") (pinfunction "PP_TP") (pintype "input"))
    )
    (net (code "14") (name "Net-(1L-KL)") (class "Default")
      (node (ref "1") (pin "9") (pinfunction "KL_9") (pintype "passive"))
      (node (ref "D10") (pin "1") (pinfunction "+_1") (pintype "passive"))
      (node (ref "TP9") (pin "TP") (pinfunction "PP_TP") (pintype "input"))
      (node (ref "X1") (pin "17") (pinfunction "17_17") (pintype "passive"))
    )
    (net (code "15") (name "Net-(2B-KL)") (class "Default")
      (node (ref "2") (pin "10") (pinfunction "KL_10") (pintype "passive"))
      (node (ref "TP25") (pin "TP") (pinfunction "PP_TP") (pintype "input"))
      (node (ref "X1") (pin "15") (pinfunction "15_15") (pintype "passive"))
    )
    (net (code "16") (name "Net-(2C-KL)") (class "Default")
      (node (ref "2") (pin "11") (pinfunction "KL_11") (pintype "passive"))
      (node (ref "R23") (pin "1") (pinfunction "1_1") (pintype "passive"))
      (node (ref "R3") (pin "1") (pinfunction "1_1") (pintype "passive"))
      (node (ref "TP26") (pin "TP") (pinfunction "PP_TP") (pintype "input"))
    )
    (net (code "17") (name "Net-(2D-KL)") (class "Default")
      (node (ref "2") (pin "12") (pinfunction "KL_12") (pintype "passive"))
      (node (ref "R35") (pin "1") (pinfunction "1_1") (pintype "passive"))
      (node (ref "TP13") (pin "TP") (pinfunction "PP_TP") (pintype "input"))
    )
    (net (code "18") (name "Net-(2E-KL)") (class "Default")
      (node (ref "2") (pin "2") (pinfunction "KL_2") (pintype "passive"))
      (node (ref "D13") (pin "2") (pinfunction "-_2") (pintype "passive"))
      (node (ref "LED1") (pin "K") (pinfunction "C_K") (pintype "passive"))
      (node (ref "TP16") (pin "TP") (pinfunction "PP_TP") (pintype "input"))
      (node (ref "X1") (pin "12") (pinfunction "12_12") (pintype "passive"))
    )
    (net (code "19") (name "Net-(2F-KL)") (class "Default")
      (node (ref "2") (pin "3") (pinfunction "KL_3") (pintype "passive"))
      (node (ref "D12") (pin "2") (pinfunction "-_2") (pintype "passive"))
      (node (ref "LED2") (pin "K") (pinfunction "C_K") (pintype "passive"))
      (node (ref "TP17") (pin "TP") (pinfunction "PP_TP") (pintype "input"))
      (node (ref "X1") (pin "11") (pinfunction "11_11") (pintype "passive"))
    )
    (net (code "20") (name "Net-(2G-KL)") (class "Default")
      (node (ref "2") (pin "4") (pinfunction "KL_4") (pintype "passive"))
      (node (ref "D2") (pin "2") (pinfunction "-_2") (pintype "passive"))
      (node (ref "LED3") (pin "K") (pinfunction "C_K") (pintype "passive"))
      (node (ref "TP18") (pin "TP") (pinfunction "PP_TP") (pintype "input"))
      (node (ref "X1") (pin "10") (pinfunction "10_10") (pintype "passive"))
    )
    (net (code "21") (name "Net-(2H-KL)") (class "Default")
      (node (ref "2") (pin "5") (pinfunction "KL_5") (pintype "passive"))
      (node (ref "D1") (pin "2") (pinfunction "-_2") (pintype "passive"))
      (node (ref "LED4") (pin "K") (pinfunction "C_K") (pintype "passive"))
      (node (ref "TP19") (pin "TP") (pinfunction "PP_TP") (pintype "input"))
      (node (ref "X1") (pin "9") (pinfunction "9_9") (pintype "passive"))
    )
    (net (code "22") (name "Net-(2I-KL)") (class "Default")
      (node (ref "2") (pin "6") (pinfunction "KL_6") (pintype "passive"))
      (node (ref "TP21") (pin "TP") (pinfunction "PP_TP") (pintype "input"))
      (node (ref "U$2") (pin "2") (pinfunction "2_2") (pintype "passive"))
    )
    (net (code "23") (name "Net-(2J-KL)") (class "Default")
      (node (ref "2") (pin "7") (pinfunction "KL_7") (pintype "passive"))
      (node (ref "LED6") (pin "A") (pinfunction "A_A") (pintype "passive"))
      (node (ref "TP22") (pin "TP") (pinfunction "PP_TP") (pintype "input"))
      (node (ref "X1") (pin "8") (pinfunction "8_8") (pintype "passive"))
    )
    (net (code "24") (name "Net-(2K-KL)") (class "Default")
      (node (ref "2") (pin "8") (pinfunction "KL_8") (pintype "passive"))
      (node (ref "D14") (pin "2") (pinfunction "-_2") (pintype "passive"))
      (node (ref "LED7") (pin "K") (pinfunction "C_K") (pintype "passive"))
      (node (ref "TP23") (pin "TP") (pinfunction "PP_TP") (pintype "input"))
      (node (ref "X1") (pin "14") (pinfunction "14_14") (pintype "passive"))
    )
    (net (code "25") (name "Net-(2L-KL)") (class "Default")
      (node (ref "2") (pin "9") (pinfunction "KL_9") (pintype "passive"))
      (node (ref "D12") (pin "1") (pinfunction "+_1") (pintype "passive"))
      (node (ref "D2") (pin "1") (pinfunction "+_1") (pintype "passive"))
      (node (ref "JP2") (pin "1") (pinfunction "1_1") (pintype "passive"))
      (node (ref "JP4") (pin "2") (pinfunction "2_2") (pintype "passive"))
      (node (ref "TP24") (pin "TP") (pinfunction "PP_TP") (pintype "input"))
    )
    (net (code "26") (name "Net-(C2-Pad1)") (class "Default")
      (node (ref "C2") (pin "1") (pinfunction "1_1") (pintype "passive"))
      (node (ref "R10") (pin "1") (pinfunction "1_1") (pintype "passive"))
      (node (ref "R12") (pin "2") (pinfunction "2_2") (pintype "passive"))
    )
    (net (code "27") (name "Net-(C11-Pad1)") (class "Default")
      (node (ref "C11") (pin "1") (pinfunction "1_1") (pintype "passive"))
      (node (ref "R42") (pin "1") (pinfunction "1_1") (pintype "passive"))
      (node (ref "R43") (pin "1") (pinfunction "1_1") (pintype "passive"))
    )
    (net (code "28") (name "Net-(D1-+)") (class "Default")
      (node (ref "D1") (pin "1") (pinfunction "+_1") (pintype "passive"))
      (node (ref "R27") (pin "1") (pinfunction "1_1") (pintype "passive"))
    )
    (net (code "29") (name "Net-(D3-+)") (class "Default")
      (node (ref "D3") (pin "1") (pinfunction "+_1") (pintype "passive"))
      (node (ref "R33") (pin "1") (pinfunction "1_1") (pintype "passive"))
    )
    (net (code "30") (name "Net-(D3--)") (class "Default")
      (node (ref "C1") (pin "2") (pinfunction "2_2") (pintype "passive"))
      (node (ref "D3") (pin "2") (pinfunction "-_2") (pintype "passive"))
      (node (ref "IC5") (pin "2") (pinfunction "TR_2") (pintype "input"))
      (node (ref "IC5") (pin "6") (pinfunction "THR_6") (pintype "input"))
      (node (ref "R24") (pin "1") (pinfunction "1_1") (pintype "passive"))
    )
    (net (code "31") (name "Net-(D8-+)") (class "Default")
      (node (ref "D8") (pin "1") (pinfunction "+_1") (pintype "passive"))
      (node (ref "R17") (pin "1") (pinfunction "1_1") (pintype "passive"))
    )
    (net (code "32") (name "Net-(D8--)") (class "Default")
      (node (ref "D8") (pin "2") (pinfunction "-_2") (pintype "passive"))
      (node (ref "IC7") (pin "2") (pinfunction "OUT_2") (pintype "open_collector"))
      (node (ref "Q10") (pin "1") (pinfunction "G_1") (pintype "passive"))
      (node (ref "R22") (pin "2") (pinfunction "2_2") (pintype "passive"))
      (node (ref "U$2") (pin "1") (pinfunction "1_1") (pintype "passive"))
    )
    (net (code "33") (name "Net-(D13-+)") (class "Default")
      (node (ref "D13") (pin "1") (pinfunction "+_1") (pintype "passive"))
      (node (ref "JP2") (pin "2") (pinfunction "2_2") (pintype "passive"))
    )
    (net (code "34") (name "Net-(D14-+)") (class "Default")
      (node (ref "D14") (pin "1") (pinfunction "+_1") (pintype "passive"))
      (node (ref "JP4") (pin "1") (pinfunction "1_1") (pintype "passive"))
    )
    (net (code "35") (name "Net-(D15--)") (class "Default")
      (node (ref "D15") (pin "2") (pinfunction "-_2") (pintype "passive"))
      (node (ref "Q1") (pin "2") (pinfunction "C_2") (pintype "passive"))
      (node (ref "Q3") (pin "2") (pinfunction "C_2") (pintype "passive"))
      (node (ref "START") (pin "TP") (pinfunction "PP_TP") (pintype "input"))
      (node (ref "X1") (pin "5") (pinfunction "5_5") (pintype "passive"))
    )
    (net (code "36") (name "Net-(IC3A-A)") (class "Default")
      (node (ref "IC3") (pin "10") (pinfunction "A_10") (pintype "input"))
      (node (ref "R31") (pin "1") (pinfunction "1_1") (pintype "passive"))
      (node (ref "X1") (pin "4") (pinfunction "4_4") (pintype "passive"))
      (node (ref "X3") (pin "2") (pinfunction "S_2") (pintype "passive"))
    )
    (net (code "37") (name "Net-(IC3A-B)") (class "Default")
      (node (ref "IC3") (pin "13") (pinfunction "B_13") (pintype "input"))
      (node (ref "R30") (pin "1") (pinfunction "1_1") (pintype "passive"))
      (node (ref "X1") (pin "3") (pinfunction "3_3") (pintype "passive"))
      (node (ref "X3") (pin "3") (pinfunction "S_3") (pintype "passive"))
    )
    (net (code "38") (name "Net-(IC3A-C)") (class "Default")
      (node (ref "IC3") (pin "12") (pinfunction "C_12") (pintype "input"))
      (node (ref "R29") (pin "1") (pinfunction "1_1") (pintype "passive"))
      (node (ref "X1") (pin "2") (pinfunction "2_2") (pintype "passive"))
      (node (ref "X3") (pin "4") (pinfunction "S_4") (pintype "passive"))
    )
    (net (code "39") (name "Net-(IC3A-Q0)") (class "Default")
      (node (ref "IC3") (pin "3") (pinfunction "Q0_3") (pintype "output"))
      (node (ref "IC6") (pin "1") (pinfunction "I1_1") (pintype "input"))
      (node (ref "IC6") (pin "2") (pinfunction "I2_2") (pintype "input"))
      (node (ref "Q11") (pin "1") (pinfunction "G_1") (pintype "passive"))
    )
    (net (code "40") (name "Net-(IC3A-Q1)") (class "Default")
      (node (ref "IC3") (pin "14") (pinfunction "Q1_14") (pintype "output"))
      (node (ref "IC6") (pin "6") (pinfunction "I6_6") (pintype "input"))
    )
    (net (code "41") (name "Net-(IC3A-Q2)") (class "Default")
      (node (ref "IC3") (pin "2") (pinfunction "Q2_2") (pintype "output"))
      (node (ref "IC6") (pin "7") (pinfunction "I7_7") (pintype "input"))
    )
    (net (code "42") (name "Net-(IC3A-Q3)") (class "Default")
      (node (ref "IC3") (pin "15") (pinfunction "Q3_15") (pintype "output"))
      (node (ref "IC6") (pin "5") (pinfunction "I5_5") (pintype "input"))
    )
    (net (code "43") (name "Net-(IC3A-Q4)") (class "Default")
      (node (ref "IC3") (pin "1") (pinfunction "Q4_1") (pintype "output"))
      (node (ref "IC6") (pin "4") (pinfunction "I4_4") (pintype "input"))
    )
    (net (code "44") (name "Net-(IC3A-Q5)") (class "Default")
      (node (ref "IC3") (pin "6") (pinfunction "Q5_6") (pintype "output"))
      (node (ref "IC6") (pin "3") (pinfunction "I3_3") (pintype "input"))
    )
    (net (code "45") (name "Net-(IC4-ADJ)") (class "Default")
      (node (ref "IC4") (pin "1") (pinfunction "ADJ_1") (pintype "input"))
      (node (ref "R18") (pin "1") (pinfunction "1_1") (pintype "passive"))
      (node (ref "R5") (pin "2") (pinfunction "2_2") (pintype "passive"))
      (node (ref "X1") (pin "7") (pinfunction "7_7") (pintype "passive"))
    )
    (net (code "46") (name "Net-(IC4-VI)") (class "Default")
      (node (ref "IC4") (pin "3") (pinfunction "VI_3") (pintype "input"))
      (node (ref "Q2") (pin "2") (pinfunction "C_2") (pintype "passive"))
      (node (ref "Q4") (pin "2") (pinfunction "C_2") (pintype "passive"))
    )
    (net (code "47") (name "Net-(IC4-VO)") (class "Default")
      (node (ref "IC4") (pin "2") (pinfunction "VO_2") (pintype "passive"))
      (node (ref "R18") (pin "2") (pinfunction "2_2") (pintype "passive"))
    )
    (net (code "48") (name "Net-(IC5-CV)") (class "Default")
      (node (ref "IC5") (pin "5") (pinfunction "CV_5") (pintype "input"))
      (node (ref "R26") (pin "2") (pinfunction "2_2") (pintype "passive"))
    )
    (net (code "49") (name "Net-(IC5-Q)") (class "Default")
      (node (ref "IC5") (pin "3") (pinfunction "Q_3") (pintype "output"))
      (node (ref "IC8") (pin "12") (pinfunction "A_12") (pintype "input"))
      (node (ref "R26") (pin "1") (pinfunction "1_1") (pintype "passive"))
    )
    (net (code "50") (name "Net-(IC6-O1)") (class "Default")
      (node (ref "IC6") (pin "16") (pinfunction "O1_16") (pintype "open_collector"))
      (node (ref "Q9") (pin "2") (pinfunction "C_2") (pintype "passive"))
      (node (ref "R3") (pin "2") (pinfunction "2_2") (pintype "passive"))
      (node (ref "T3") (pin "C") (pinfunction "C_C") (pintype "passive"))
      (node (ref "X1") (pin "21") (pinfunction "21_21") (pintype "passive"))
    )
    (net (code "51") (name "Net-(IC6-O2)") (class "Default")
      (node (ref "IC6") (pin "15") (pinfunction "O2_15") (pintype "open_collector"))
      (node (ref "R13") (pin "1") (pinfunction "1_1") (pintype "passive"))
    )
    (net (code "52") (name "Net-(IC7A-+IN)") (class "Default")
      (node (ref "IC7") (pin "5") (pinfunction "+IN_5") (pintype "input"))
      (node (ref "R15") (pin "1") (pinfunction "1_1") (pintype "passive"))
      (node (ref "R16") (pin "2") (pinfunction "2_2") (pintype "passive"))
      (node (ref "R17") (pin "2") (pinfunction "2_2") (pintype "passive"))
    )
    (net (code "53") (name "Net-(IC7A--IN)") (class "Default")
      (node (ref "C3") (pin "1") (pinfunction "1_1") (pintype "passive"))
      (node (ref "IC7") (pin "4") (pinfunction "-IN_4") (pintype "input"))
      (node (ref "R12") (pin "1") (pinfunction "1_1") (pintype "passive"))
    )
    (net (code "54") (name "Net-(IC7B-+IN)") (class "Default")
      (node (ref "IC7") (pin "7") (pinfunction "+IN_7") (pintype "input"))
      (node (ref "R25") (pin "1") (pinfunction "1_1") (pintype "passive"))
      (node (ref "R6") (pin "1") (pinfunction "1_1") (pintype "passive"))
    )
    (net (code "55") (name "Net-(IC7B--IN)") (class "Default")
      (node (ref "IC7") (pin "6") (pinfunction "-IN_6") (pintype "input"))
      (node (ref "IC7") (pin "8") (pinfunction "-IN_8") (pintype "input"))
      (node (ref "R5") (pin "1") (pinfunction "1_1") (pintype "passive"))
    )
    (net (code "56") (name "Net-(IC7B-OUT)") (class "Default")
      (node (ref "IC7") (pin "1") (pinfunction "OUT_1") (pintype "open_collector"))
      (node (ref "R10") (pin "2") (pinfunction "2_2") (pintype "passive"))
      (node (ref "R19") (pin "2") (pinfunction "2_2") (pintype "passive"))
    )
    (net (code "57") (name "Net-(IC7C-+IN)") (class "Default")
      (node (ref "C5") (pin "1") (pinfunction "1_1") (pintype "passive"))
      (node (ref "IC7") (pin "9") (pinfunction "+IN_9") (pintype "input"))
      (node (ref "R25") (pin "2") (pinfunction "2_2") (pintype "passive"))
      (node (ref "R8") (pin "2") (pinfunction "2_2") (pintype "passive"))
    )
    (net (code "58") (name "Net-(IC7C-OUT)") (class "Default")
      (node (ref "C9") (pin "2") (pinfunction "2_2") (pintype "passive"))
      (node (ref "IC7") (pin "14") (pinfunction "OUT_14") (pintype "open_collector"))
      (node (ref "R9") (pin "2") (pinfunction "2_2") (pintype "passive"))
    )
    (net (code "59") (name "Net-(IC8B-B)") (class "Default")
      (node (ref "IC8") (pin "11") (pinfunction "B_11") (pintype "input"))
      (node (ref "IC8") (pin "9") (pinfunction "~{Q}_9") (pintype "output"))
      (node (ref "R35") (pin "2") (pinfunction "2_2") (pintype "passive"))
    )
    (net (code "60") (name "Net-(IC8B-T2)") (class "Default")
      (node (ref "C10") (pin "1") (pinfunction "1_1") (pintype "passive"))
      (node (ref "IC8") (pin "14") (pinfunction "T2_14") (pintype "input"))
      (node (ref "R34") (pin "1") (pinfunction "1_1") (pintype "passive"))
    )
    (net (code "61") (name "Net-(IC10A-+IN)") (class "Default")
      (node (ref "C8") (pin "1") (pinfunction "1_1") (pintype "passive"))
      (node (ref "IC10") (pin "3") (pinfunction "+IN_3") (pintype "input"))
      (node (ref "R1") (pin "1") (pinfunction "1_1") (pintype "passive"))
    )
    (net (code "62") (name "Net-(IC10A--IN)") (class "Default")
      (node (ref "IC10") (pin "2") (pinfunction "-IN_2") (pintype "input"))
      (node (ref "R2") (pin "2") (pinfunction "2_2") (pintype "passive"))
    )
    (net (code "63") (name "Net-(IC10A-OUT)") (class "Default")
      (node (ref "IC10") (pin "1") (pinfunction "OUT_1") (pintype "output"))
      (node (ref "R42") (pin "2") (pinfunction "2_2") (pintype "passive"))
    )
    (net (code "64") (name "Net-(IC10B-+IN)") (class "Default")
      (node (ref "IC10") (pin "5") (pinfunction "+IN_5") (pintype "input"))
      (node (ref "R43") (pin "2") (pinfunction "2_2") (pintype "passive"))
      (node (ref "R44") (pin "2") (pinfunction "2_2") (pintype "passive"))
    )
    (net (code "65") (name "Net-(IC10B--IN)") (class "Default")
      (node (ref "IC10") (pin "6") (pinfunction "-IN_6") (pintype "input"))
      (node (ref "R45") (pin "1") (pinfunction "1_1") (pintype "passive"))
      (node (ref "R46") (pin "2") (pinfunction "2_2") (pintype "passive"))
    )
    (net (code "66") (name "Net-(IC10B-OUT)") (class "Default")
      (node (ref "IC10") (pin "7") (pinfunction "OUT_7") (pintype "output"))
      (node (ref "R32") (pin "1") (pinfunction "1_1") (pintype "passive"))
      (node (ref "R44") (pin "1") (pinfunction "1_1") (pintype "passive"))
    )
    (net (code "67") (name "Net-(JP1-Pad2)") (class "Default")
      (node (ref "JP1") (pin "2") (pinfunction "2_2") (pintype "passive"))
      (node (ref "R36") (pin "2") (pinfunction "2_2") (pintype "passive"))
      (node (ref "R37") (pin "2") (pinfunction "2_2") (pintype "passive"))
    )
    (net (code "68") (name "Net-(JP3-Pad1)") (class "Default")
      (node (ref "JP3") (pin "1") (pinfunction "1_1") (pintype "passive"))
      (node (ref "R23") (pin "2") (pinfunction "2_2") (pintype "passive"))
    )
    (net (code "69") (name "Net-(LED1-PadA)") (class "Default")
      (node (ref "LED1") (pin "A") (pinfunction "A_A") (pintype "passive"))
      (node (ref "LED2") (pin "A") (pinfunction "A_A") (pintype "passive"))
      (node (ref "LED3") (pin "A") (pinfunction "A_A") (pintype "passive"))
      (node (ref "LED4") (pin "A") (pinfunction "A_A") (pintype "passive"))
      (node (ref "LED7") (pin "A") (pinfunction "A_A") (pintype "passive"))
      (node (ref "R11") (pin "1") (pinfunction "1_1") (pintype "passive"))
    )
    (net (code "70") (name "Net-(LED6-C)") (class "Default")
      (node (ref "LED6") (pin "K") (pinfunction "C_K") (pintype "passive"))
      (node (ref "R4") (pin "1") (pinfunction "1_1") (pintype "passive"))
    )
    (net (code "71") (name "Net-(Q1-B)") (class "Default")
      (node (ref "Q1") (pin "1") (pinfunction "B_1") (pintype "passive"))
      (node (ref "Q3") (pin "1") (pinfunction "B_1") (pintype "passive"))
      (node (ref "R13") (pin "2") (pinfunction "2_2") (pintype "passive"))
    )
    (net (code "72") (name "Net-(Q2-B)") (class "Default")
      (node (ref "Q2") (pin "1") (pinfunction "B_1") (pintype "passive"))
      (node (ref "Q4") (pin "1") (pinfunction "B_1") (pintype "passive"))
      (node (ref "R9") (pin "1") (pinfunction "1_1") (pintype "passive"))
    )
    (net (code "73") (name "Net-(Q5-B)") (class "Default")
      (node (ref "Q5") (pin "1") (pinfunction "B_1") (pintype "passive"))
      (node (ref "Q6") (pin "1") (pinfunction "B_1") (pintype "passive"))
      (node (ref "Q6") (pin "2") (pinfunction "C_2") (pintype "passive"))
      (node (ref "Q7") (pin "1") (pinfunction "B_1") (pintype "passive"))
      (node (ref "Q7") (pin "2") (pinfunction "C_2") (pintype "passive"))
      (node (ref "Q8") (pin "1") (pinfunction "B_1") (pintype "passive"))
      (node (ref "R38") (pin "1") (pinfunction "1_1") (pintype "passive"))
      (node (ref "R39") (pin "1") (pinfunction "1_1") (pintype "passive"))
      (node (ref "T1") (pin "2") (pinfunction "B_2") (pintype "passive"))
      (node (ref "T1") (pin "4") (pinfunction "B_4") (pintype "passive"))
      (node (ref "T1") (pin "6") (pinfunction "C1_6") (pintype "passive"))
      (node (ref "X2") (pin "2") (pinfunction "S_2") (pintype "passive"))
    )
    (net (code "74") (name "Net-(Q5-E)") (class "Default")
      (node (ref "Q5") (pin "3") (pinfunction "E_3") (pintype "passive"))
      (node (ref "Q8") (pin "3") (pinfunction "E_3") (pintype "passive"))
      (node (ref "R21") (pin "2") (pinfunction "2_2") (pintype "passive"))
      (node (ref "T1") (pin "1") (pinfunction "E_1") (pintype "passive"))
    )
    (net (code "75") (name "Net-(Q6-E)") (class "Default")
      (node (ref "Q6") (pin "3") (pinfunction "E_3") (pintype "passive"))
      (node (ref "Q7") (pin "3") (pinfunction "E_3") (pintype "passive"))
      (node (ref "R20") (pin "2") (pinfunction "2_2") (pintype "passive"))
      (node (ref "T1") (pin "3") (pinfunction "E_3") (pintype "passive"))
    )
    (net (code "76") (name "Net-(Q9-B)") (class "Default")
      (node (ref "Q9") (pin "1") (pinfunction "B_1") (pintype "passive"))
      (node (ref "R32") (pin "2") (pinfunction "2_2") (pintype "passive"))
      (node (ref "T3") (pin "B") (pinfunction "B_B") (pintype "passive"))
    )
    (net (code "77") (name "Net-(Q10-D)") (class "Default")
      (node (ref "Q10") (pin "3") (pinfunction "D_3") (pintype "passive"))
      (node (ref "R7") (pin "2") (pinfunction "2_2") (pintype "passive"))
    )
    (net (code "78") (name "Net-(R1-Pad2)") (class "Default")
      (node (ref "R1") (pin "2") (pinfunction "2_2") (pintype "passive"))
      (node (ref "X1") (pin "22") (pinfunction "22_22") (pintype "passive"))
    )
    (net (code "79") (name "Net-(R14-Pad1)") (class "Default")
      (node (ref "R14") (pin "1") (pinfunction "1_1") (pintype "passive"))
      (node (ref "R7") (pin "1") (pinfunction "1_1") (pintype "passive"))
      (node (ref "U$2") (pin "3") (pinfunction "3_3") (pintype "passive"))
    )
    (net (code "80") (name "Net-(R27-Pad2)") (class "Default")
      (node (ref "R27") (pin "2") (pinfunction "2_2") (pintype "passive"))
      (node (ref "R28") (pin "1") (pinfunction "1_1") (pintype "passive"))
    )
    (net (code "81") (name "Net-(R33-Pad2)") (class "Default")
      (node (ref "R33") (pin "2") (pinfunction "2_2") (pintype "passive"))
      (node (ref "X1") (pin "16") (pinfunction "16_16") (pintype "passive"))
    )
    (net (code "82") (name "Net-(TACHO_BEL-PP)") (class "Default")
      (node (ref "TACHO_BEL") (pin "TP") (pinfunction "PP_TP") (pintype "input"))
      (node (ref "X1") (pin "24") (pinfunction "24_24") (pintype "passive"))
    )
    (net (code "83") (name "VCC") (class "Default")
      (node (ref "6V") (pin "TP") (pinfunction "PP_TP") (pintype "input"))
      (node (ref "C4") (pin "1") (pinfunction "1_1") (pintype "passive"))
      (node (ref "IC1") (pin "OUT") (pinfunction "OUT_OUT") (pintype "passive"))
      (node (ref "IC10") (pin "8") (pinfunction "V+_8") (pintype "power_in"))
      (node (ref "IC2") (pin "1") (pinfunction "OUT_1") (pintype "passive"))
      (node (ref "IC7") (pin "3") (pinfunction "V+_3") (pintype "power_in"))
      (node (ref "R11") (pin "2") (pinfunction "2_2") (pintype "passive"))
      (node (ref "R15") (pin "2") (pinfunction "2_2") (pintype "passive"))
      (node (ref "R19") (pin "1") (pinfunction "1_1") (pintype "passive"))
      (node (ref "R45") (pin "2") (pinfunction "2_2") (pintype "passive"))
      (node (ref "R6") (pin "2") (pinfunction "2_2") (pintype "passive"))
    )
    (net (code "84") (name "unconnected-(IC3A-Q6-Pad7)") (class "Default")
      (node (ref "IC3") (pin "7") (pinfunction "Q6_7") (pintype "output"))
    )
    (net (code "85") (name "unconnected-(IC3A-Q7-Pad4)") (class "Default")
      (node (ref "IC3") (pin "4") (pinfunction "Q7_4") (pintype "output"))
    )
    (net (code "86") (name "unconnected-(IC3A-Q8-Pad9)") (class "Default")
      (node (ref "IC3") (pin "9") (pinfunction "Q8_9") (pintype "output"))
    )
    (net (code "87") (name "unconnected-(IC3A-Q9-Pad5)") (class "Default")
      (node (ref "IC3") (pin "5") (pinfunction "Q9_5") (pintype "output"))
    )
    (net (code "88") (name "unconnected-(IC5-DIS-Pad7)") (class "Default")
      (node (ref "IC5") (pin "7") (pinfunction "DIS_7") (pintype "input"))
    )
    (net (code "89") (name "unconnected-(IC6-CD+-Pad9)") (class "Default")
      (node (ref "IC6") (pin "9") (pinfunction "CD+_9") (pintype "passive"))
    )
    (net (code "90") (name "unconnected-(IC7D-OUT-Pad13)") (class "Default")
      (node (ref "IC7") (pin "13") (pinfunction "OUT_13") (pintype "open_collector"))
    )
    (net (code "91") (name "unconnected-(IC8A-Q-Pad6)") (class "Default")
      (node (ref "IC8") (pin "6") (pinfunction "Q_6") (pintype "output"))
    )
    (net (code "92") (name "unconnected-(IC8A-T2-Pad2)") (class "Default")
      (node (ref "IC8") (pin "2") (pinfunction "T2_2") (pintype "input"))
    )
    (net (code "93") (name "unconnected-(IC8A-~{Q}-Pad7)") (class "Default")
      (node (ref "IC8") (pin "7") (pinfunction "~{Q}_7") (pintype "output"))
    )
    (net (code "94") (name "unconnected-(IC8B-Q-Pad10)") (class "Default")
      (node (ref "IC8") (pin "10") (pinfunction "Q_10") (pintype "output"))
    )
    (net (code "95") (name "unconnected-(JP5-Pad1)") (class "Default")
      (node (ref "JP5") (pin "1") (pinfunction "1_1") (pintype "passive"))
    )
    (net (code "96") (name "unconnected-(JP5-Pad2)") (class "Default")
      (node (ref "JP5") (pin "2") (pinfunction "2_2") (pintype "passive"))
    )
    (net (code "97") (name "unconnected-(Q3-C{slash}-Pad4)") (class "Default")
      (node (ref "Q3") (pin "4") (pinfunction "C/_4") (pintype "passive"))
    )
    (net (code "98") (name "unconnected-(Q4-C{slash}-Pad4)") (class "Default")
      (node (ref "Q4") (pin "4") (pinfunction "C/_4") (pintype "passive"))
    )
    (net (code "99") (name "unconnected-(Q5-C{slash}-Pad4)") (class "Default")
      (node (ref "Q5") (pin "4") (pinfunction "C/_4") (pintype "passive"))
    )
    (net (code "100") (name "unconnected-(Q6-C{slash}-Pad4)") (class "Default")
      (node (ref "Q6") (pin "4") (pinfunction "C/_4") (pintype "passive"))
    )
    (net (code "101") (name "unconnected-(T1A-C-Pad5)") (class "Default")
      (node (ref "T1") (pin "5") (pinfunction "C_5") (pintype "passive"))
    )
    (net (code "102") (name "unconnected-(T1B-C-Pad7)") (class "Default")
      (node (ref "T1") (pin "7") (pinfunction "C_7") (pintype "passive"))
    )
    (net (code "103") (name "unconnected-(X1-Pad20)") (class "Default")
      (node (ref "X1") (pin "20") (pinfunction "20_20") (pintype "passive"))
    )
  )
)
